# 512KBits_I2C_EEPROM.net
KiCad netlist of a schematic drawn in Altium Designer
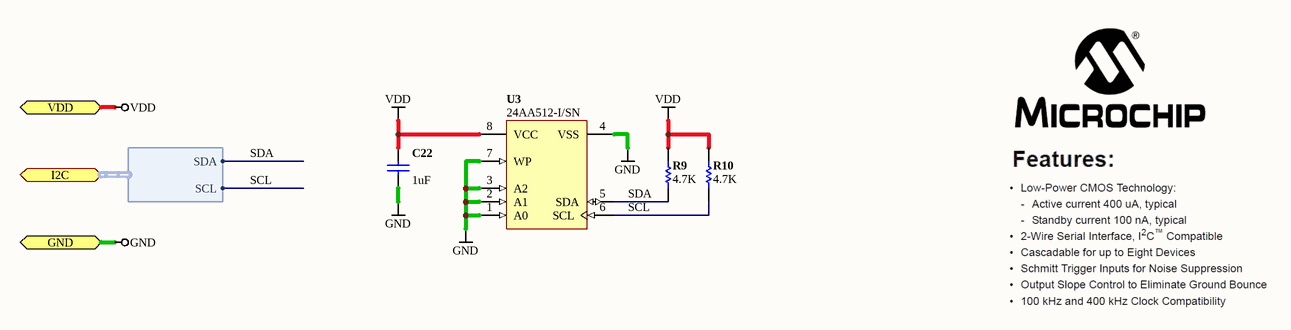
[diagram p0: 512KBits_I2C_EEPROM.SchDoc]

(export (version "E")
  (design (tool "Eeschema 10.0.6"))
  (components
    (comp (ref "C22")
      (value "1uF")
      (footprint "CAPC0402(1005)60_N")
      (description "CAP 1uF 6.3V ±10% 0402 (1005 Metric) Thickness 0.6mm SMD")
      (fields (field (name "TOLERANCE") "±10%") (field (name "Comment") "CAP 1uF 6.3V 0402(1005)"))
      (libsource (lib "Altium Content Vault") (part "CMP-1034-02113-1"))
    )
    (comp (ref "R9")
      (value "4.7K")
      (footprint "RESC0402(1005)_N")
      (description "4K7 0.063W 5% 0402 (1005 Metric)  SMD")
      (fields (field (name "TOLERANCE") "5 %") (field (name "POWER") "0.063 W"))
      (libsource (lib "Altium Content Vault") (part "CMP-1011-00090-1"))
    )
    (comp (ref "R10")
      (value "4.7K")
      (footprint "RESC0402(1005)_N")
      (description "4K7 0.063W 5% 0402 (1005 Metric)  SMD")
      (fields (field (name "TOLERANCE") "5 %") (field (name "POWER") "0.063 W"))
      (libsource (lib "Altium Content Vault") (part "CMP-1011-00090-1"))
    )
    (comp (ref "U3")
      (value "24AA512-I/SN")
      (footprint "MCHP-SOIC-SN8_N")
      (description "512K bits I2C™ Serial EEPROM, 1.7 to 5.5 V, 400 kHz, -40 to 85 degC, 8-pin SOIC (SN8), Tube")
      (fields (field (name "MANUFACTURER") "Microchip"))
      (libsource (lib "Altium Content Vault") (part "MCHP-24-AA-FC512-SOIC-TSSOP-8"))
    )
  )
  (nets
    (net (code "2") (name "/SCL") (class "Default")
      (node (ref "R10") (pin "1") (pinfunction "1_1") (pintype "passive"))
      (node (ref "U3") (pin "6") (pinfunction "SCL_6") (pintype "input"))
    )
    (net (code "3") (name "/SDA") (class "Default")
      (node (ref "R9") (pin "1") (pinfunction "1_1") (pintype "passive"))
      (node (ref "U3") (pin "5") (pinfunction "SDA_5") (pintype "bidirectional"))
    )
    (net (code "5") (name "GND") (class "Default")
      (node (ref "C22") (pin "1") (pinfunction "1_1") (pintype "passive"))
      (node (ref "U3") (pin "1") (pinfunction "A0_1") (pintype "input"))
      (node (ref "U3") (pin "2") (pinfunction "A1_2") (pintype "input"))
      (node (ref "U3") (pin "3") (pinfunction "A2_3") (pintype "input"))
      (node (ref "U3") (pin "4") (pinfunction "VSS_4") (pintype "power_in"))
      (node (ref "U3") (pin "7") (pinfunction "WP_7") (pintype "input"))
    )
    (net (code "6") (name "VDD") (class "Default")
      (node (ref "C22") (pin "2") (pinfunction "2_2") (pintype "passive"))
      (node (ref "R10") (pin "2") (pinfunction "2_2") (pintype "passive"))
      (node (ref "R9") (pin "2") (pinfunction "2_2") (pintype "passive"))
      (node (ref "U3") (pin "8") (pinfunction "VCC_8") (pintype "power_in"))
    )
  )
)
